# main.net
KiCad netlist of a schematic drawn in EAGLE
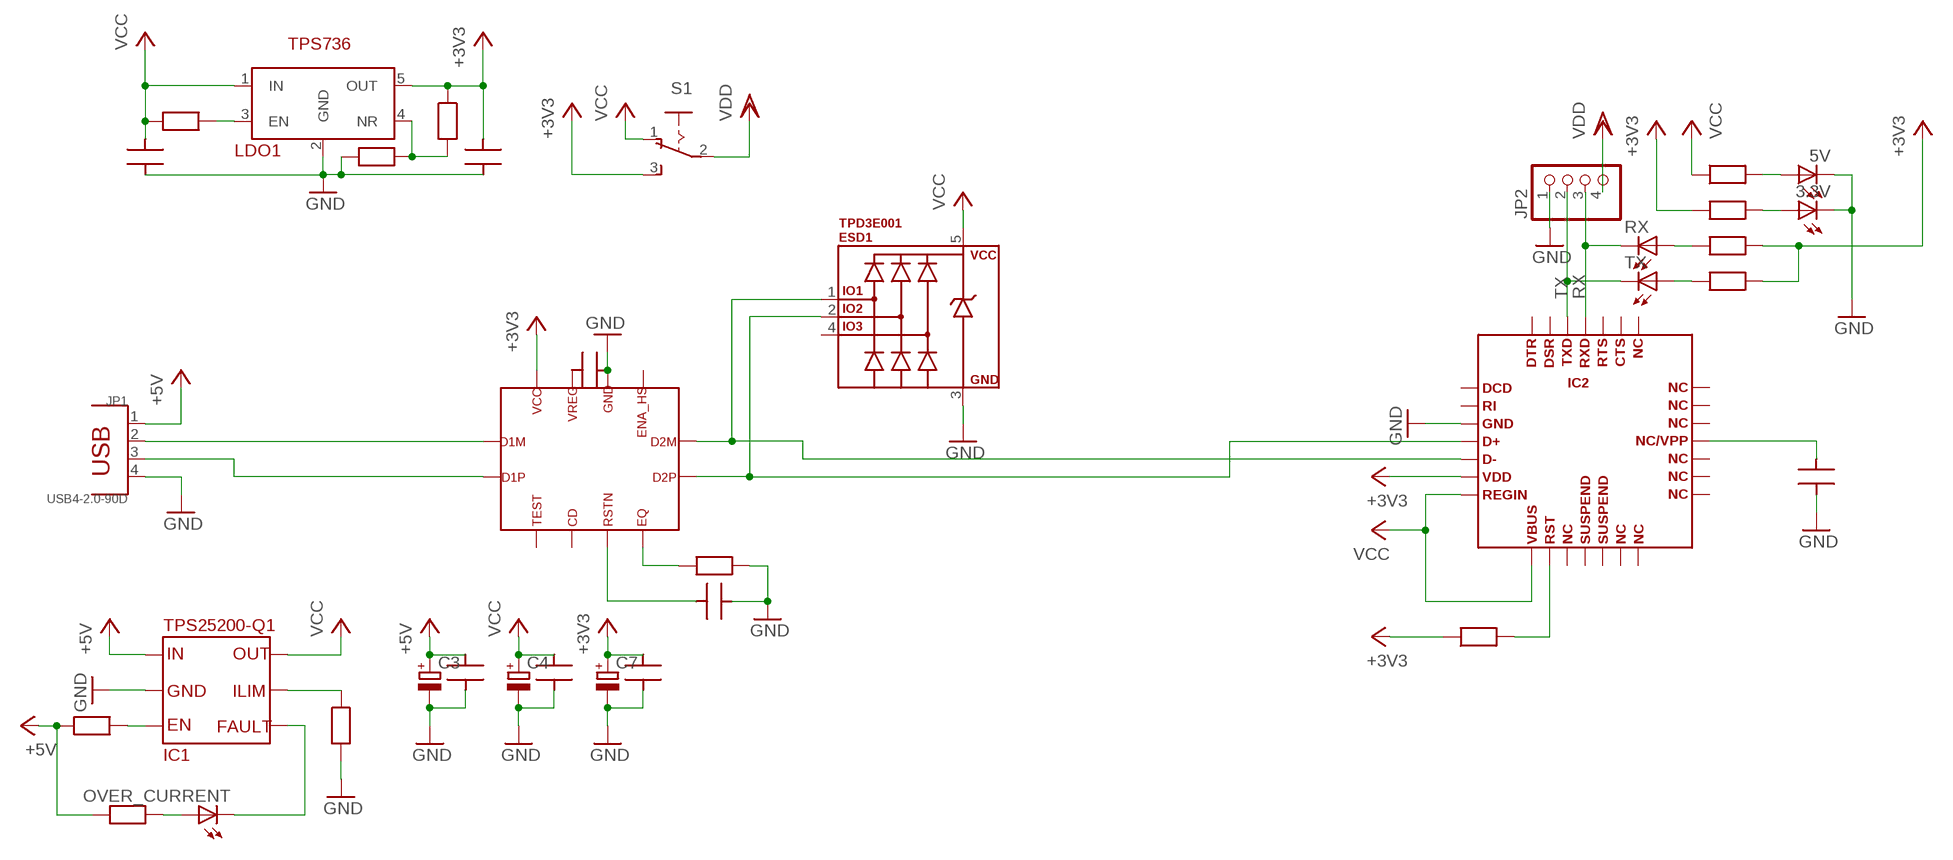
[diagram p0: schematic, sheet 1]

(export (version "E")
  (design (tool "Eeschema 10.0.6"))
  (components
    (comp (ref "3.3V")
      (value "LEDCHIP-LED0603")
      (footprint "eagle-import:CHIP-LED0603")
      (libsource (lib "eagle-import") (part "LEDCHIP-LED0603"))
    )
    (comp (ref "5V")
      (value "LEDCHIP-LED0603")
      (footprint "eagle-import:CHIP-LED0603")
      (libsource (lib "eagle-import") (part "LEDCHIP-LED0603"))
    )
    (comp (ref "C1")
      (value "CAP0603")
      (footprint "eagle-import:C0603")
      (libsource (lib "eagle-import") (part "CAP0603"))
    )
    (comp (ref "C2")
      (value "CAP0603")
      (footprint "eagle-import:C0603")
      (libsource (lib "eagle-import") (part "CAP0603"))
    )
    (comp (ref "C3")
      (value "CPOL-EUSMCA")
      (footprint "eagle-import:SMC_A")
      (libsource (lib "eagle-import") (part "CPOL-EUSMCA"))
    )
    (comp (ref "C4")
      (value "CPOL-EUSMCA")
      (footprint "eagle-import:SMC_A")
      (libsource (lib "eagle-import") (part "CPOL-EUSMCA"))
    )
    (comp (ref "C5")
      (value "CAP0603")
      (footprint "eagle-import:C0603")
      (libsource (lib "eagle-import") (part "CAP0603"))
    )
    (comp (ref "C6")
      (value "CAP0603")
      (footprint "eagle-import:C0603")
      (libsource (lib "eagle-import") (part "CAP0603"))
    )
    (comp (ref "C7")
      (value "CPOL-EUSMCA")
      (footprint "eagle-import:SMC_A")
      (libsource (lib "eagle-import") (part "CPOL-EUSMCA"))
    )
    (comp (ref "C8")
      (value "CAP0603")
      (footprint "eagle-import:C0603")
      (libsource (lib "eagle-import") (part "CAP0603"))
    )
    (comp (ref "C9")
      (value "CAP0603")
      (footprint "eagle-import:C0603")
      (libsource (lib "eagle-import") (part "CAP0603"))
    )
    (comp (ref "C10")
      (value "CAP0603")
      (footprint "eagle-import:C0603")
      (libsource (lib "eagle-import") (part "CAP0603"))
    )
    (comp (ref "C11")
      (value "CAP0603")
      (footprint "eagle-import:C0603")
      (libsource (lib "eagle-import") (part "CAP0603"))
    )
    (comp (ref "ESD1")
      (value "TPD3E001")
      (footprint "eagle-import:SOT23-5")
      (libsource (lib "eagle-import") (part "TPD3E001"))
    )
    (comp (ref "IC1")
      (value "TPS25200-Q1")
      (footprint "eagle-import:PWSON6")
      (libsource (lib "eagle-import") (part "TPS25200-Q1"))
    )
    (comp (ref "IC2")
      (value "CP2102/9")
      (footprint "eagle-import:QFN-28")
      (libsource (lib "eagle-import") (part "CP2102/9"))
    )
    (comp (ref "JP1")
      (value "USB4-2.0-90D")
      (footprint "eagle-import:USB4+2P-2.0-90D")
      (libsource (lib "eagle-import") (part "DIP-USB-A-TYPE-FMAL(4+2P-2.0-90D)"))
    )
    (comp (ref "JP2")
      (value "PINHD-1X4")
      (footprint "eagle-import:1X04")
      (libsource (lib "eagle-import") (part "PINHD-1X4"))
    )
    (comp (ref "LDO1")
      (value "TPS736")
      (footprint "eagle-import:SOT23-5")
      (libsource (lib "eagle-import") (part "TPS736"))
    )
    (comp (ref "OVER_CURRENT")
      (value "LEDCHIP-LED0603")
      (footprint "eagle-import:CHIP-LED0603")
      (libsource (lib "eagle-import") (part "LEDCHIP-LED0603"))
    )
    (comp (ref "R1")
      (value "RES0603")
      (footprint "eagle-import:R0603")
      (libsource (lib "eagle-import") (part "RES0603"))
    )
    (comp (ref "R2")
      (value "RES0603")
      (footprint "eagle-import:R0603")
      (libsource (lib "eagle-import") (part "RES0603"))
    )
    (comp (ref "R3")
      (value "RES0603")
      (footprint "eagle-import:R0603")
      (libsource (lib "eagle-import") (part "RES0603"))
    )
    (comp (ref "R4")
      (value "RES0603")
      (footprint "eagle-import:R0603")
      (libsource (lib "eagle-import") (part "RES0603"))
    )
    (comp (ref "R5")
      (value "RES0603")
      (footprint "eagle-import:R0603")
      (libsource (lib "eagle-import") (part "RES0603"))
    )
    (comp (ref "R6")
      (value "RES0603")
      (footprint "eagle-import:R0603")
      (libsource (lib "eagle-import") (part "RES0603"))
    )
    (comp (ref "R7")
      (value "RES0603")
      (footprint "eagle-import:R0603")
      (libsource (lib "eagle-import") (part "RES0603"))
    )
    (comp (ref "R8")
      (value "RES0603")
      (footprint "eagle-import:R0603")
      (libsource (lib "eagle-import") (part "RES0603"))
    )
    (comp (ref "R9")
      (value "RES0603")
      (footprint "eagle-import:R0603")
      (libsource (lib "eagle-import") (part "RES0603"))
    )
    (comp (ref "R10")
      (value "RES0603")
      (footprint "eagle-import:R0603")
      (libsource (lib "eagle-import") (part "RES0603"))
    )
    (comp (ref "R11")
      (value "RES0603")
      (footprint "eagle-import:R0603")
      (libsource (lib "eagle-import") (part "RES0603"))
    )
    (comp (ref "R12")
      (value "RES0603")
      (footprint "eagle-import:R0603")
      (libsource (lib "eagle-import") (part "RES0603"))
    )
    (comp (ref "RX")
      (value "LEDCHIP-LED0603")
      (footprint "eagle-import:CHIP-LED0603")
      (libsource (lib "eagle-import") (part "LEDCHIP-LED0603"))
    )
    (comp (ref "S1")
      (value "255SB")
      (footprint "eagle-import:255SB")
      (libsource (lib "eagle-import") (part "255SB"))
    )
    (comp (ref "TX")
      (value "LEDCHIP-LED0603")
      (footprint "eagle-import:CHIP-LED0603")
      (libsource (lib "eagle-import") (part "LEDCHIP-LED0603"))
    )
    (comp (ref "USB1")
      (value "TUSB211QRWBRQ1")
      (footprint "eagle-import:X2QFN")
      (libsource (lib "eagle-import") (part "TUSB211QRWBRQ1"))
    )
  )
  (nets
    (net (code "1") (name "+3V3") (class "Default")
      (node (ref "C2") (pin "2") (pinfunction "P$2_2") (pintype "bidirectional"))
      (node (ref "C7") (pin "+") (pinfunction "+_+") (pintype "passive"))
      (node (ref "C8") (pin "2") (pinfunction "P$2_2") (pintype "bidirectional"))
      (node (ref "IC2") (pin "6") (pinfunction "P$6_6") (pintype "bidirectional"))
      (node (ref "LDO1") (pin "5") (pinfunction "OUT_5") (pintype "bidirectional"))
      (node (ref "R10") (pin "1") (pinfunction "P$1_1") (pintype "bidirectional"))
      (node (ref "R2") (pin "1") (pinfunction "P$1_1") (pintype "bidirectional"))
      (node (ref "R7") (pin "1") (pinfunction "P$1_1") (pintype "bidirectional"))
      (node (ref "R8") (pin "2") (pinfunction "P$2_2") (pintype "bidirectional"))
      (node (ref "R9") (pin "2") (pinfunction "P$2_2") (pintype "bidirectional"))
      (node (ref "S1") (pin "3") (pinfunction "S_3") (pintype "passive"))
      (node (ref "USB1") (pin "12") (pinfunction "P$12_12") (pintype "bidirectional"))
    )
    (net (code "2") (name "+5V") (class "Default")
      (node (ref "C3") (pin "+") (pinfunction "+_+") (pintype "passive"))
      (node (ref "C5") (pin "2") (pinfunction "P$2_2") (pintype "bidirectional"))
      (node (ref "IC1") (pin "P$1") (pinfunction "P$1_P$1") (pintype "bidirectional"))
      (node (ref "JP1") (pin "1") (pinfunction "1_1") (pintype "bidirectional"))
      (node (ref "R12") (pin "1") (pinfunction "P$1_1") (pintype "bidirectional"))
      (node (ref "R4") (pin "2") (pinfunction "P$2_2") (pintype "bidirectional"))
    )
    (net (code "3") (name "/RX") (class "Default")
      (node (ref "IC2") (pin "25") (pinfunction "P$25_25") (pintype "bidirectional"))
      (node (ref "JP2") (pin "3") (pinfunction "3_3") (pintype "passive"))
      (node (ref "RX") (pin "C") (pinfunction "C_C") (pintype "passive"))
    )
    (net (code "4") (name "/TX") (class "Default")
      (node (ref "IC2") (pin "26") (pinfunction "P$26_26") (pintype "bidirectional"))
      (node (ref "JP2") (pin "2") (pinfunction "2_2") (pintype "passive"))
      (node (ref "TX") (pin "C") (pinfunction "C_C") (pintype "passive"))
    )
    (net (code "5") (name "GND") (class "Default")
      (node (ref "3.3V") (pin "C") (pinfunction "C_C") (pintype "passive"))
      (node (ref "5V") (pin "C") (pinfunction "C_C") (pintype "passive"))
      (node (ref "C1") (pin "1") (pinfunction "P$1_1") (pintype "bidirectional"))
      (node (ref "C10") (pin "1") (pinfunction "P$1_1") (pintype "bidirectional"))
      (node (ref "C11") (pin "2") (pinfunction "P$2_2") (pintype "bidirectional"))
      (node (ref "C2") (pin "1") (pinfunction "P$1_1") (pintype "bidirectional"))
      (node (ref "C3") (pin "-") (pinfunction "-_-") (pintype "passive"))
      (node (ref "C4") (pin "-") (pinfunction "-_-") (pintype "passive"))
      (node (ref "C5") (pin "1") (pinfunction "P$1_1") (pintype "bidirectional"))
      (node (ref "C6") (pin "1") (pinfunction "P$1_1") (pintype "bidirectional"))
      (node (ref "C7") (pin "-") (pinfunction "-_-") (pintype "passive"))
      (node (ref "C8") (pin "1") (pinfunction "P$1_1") (pintype "bidirectional"))
      (node (ref "C9") (pin "1") (pinfunction "P$1_1") (pintype "bidirectional"))
      (node (ref "ESD1") (pin "3") (pinfunction "3_3") (pintype "bidirectional"))
      (node (ref "IC1") (pin "EPAD") (pinfunction "P$2_EPAD") (pintype "bidirectional"))
      (node (ref "IC1") (pin "P$2") (pinfunction "P$2_P$2") (pintype "bidirectional"))
      (node (ref "IC2") (pin "3") (pinfunction "P$3_3") (pintype "bidirectional"))
      (node (ref "IC2") (pin "EPAD_B") (pinfunction "P$3_EPAD_B") (pintype "bidirectional"))
      (node (ref "IC2") (pin "EPAD_T") (pinfunction "P$3_EPAD_T") (pintype "bidirectional"))
      (node (ref "IC2") (pin "EPAD_VIA1") (pinfunction "P$3_EPAD_VIA1") (pintype "bidirectional"))
      (node (ref "IC2") (pin "EPAD_VIA2") (pinfunction "P$3_EPAD_VIA2") (pintype "bidirectional"))
      (node (ref "IC2") (pin "EPAD_VIA3") (pinfunction "P$3_EPAD_VIA3") (pintype "bidirectional"))
      (node (ref "IC2") (pin "EPAD_VIA4") (pinfunction "P$3_EPAD_VIA4") (pintype "bidirectional"))
      (node (ref "IC2") (pin "EPAD_VIA5") (pinfunction "P$3_EPAD_VIA5") (pintype "bidirectional"))
      (node (ref "IC2") (pin "EPAD_VIA6") (pinfunction "P$3_EPAD_VIA6") (pintype "bidirectional"))
      (node (ref "IC2") (pin "EPAD_VIA7") (pinfunction "P$3_EPAD_VIA7") (pintype "bidirectional"))
      (node (ref "IC2") (pin "EPAD_VIA8") (pinfunction "P$3_EPAD_VIA8") (pintype "bidirectional"))
      (node (ref "IC2") (pin "EPAD_VIA9") (pinfunction "P$3_EPAD_VIA9") (pintype "bidirectional"))
      (node (ref "JP1") (pin "4") (pinfunction "4_4") (pintype "bidirectional"))
      (node (ref "JP2") (pin "1") (pinfunction "1_1") (pintype "passive"))
      (node (ref "LDO1") (pin "2") (pinfunction "GND_2") (pintype "bidirectional"))
      (node (ref "R3") (pin "1") (pinfunction "P$1_1") (pintype "bidirectional"))
      (node (ref "R5") (pin "2") (pinfunction "P$2_2") (pintype "bidirectional"))
      (node (ref "R6") (pin "2") (pinfunction "P$2_2") (pintype "bidirectional"))
      (node (ref "USB1") (pin "10") (pinfunction "P$10_10") (pintype "bidirectional"))
    )
    (net (code "6") (name "Net-(C9-P$2)") (class "Default")
      (node (ref "C9") (pin "2") (pinfunction "P$2_2") (pintype "bidirectional"))
      (node (ref "USB1") (pin "11") (pinfunction "P$11_11") (pintype "bidirectional"))
    )
    (net (code "7") (name "Net-(C10-P$2)") (class "Default")
      (node (ref "C10") (pin "2") (pinfunction "P$2_2") (pintype "bidirectional"))
      (node (ref "USB1") (pin "5") (pinfunction "P$5_5") (pintype "bidirectional"))
    )
    (net (code "8") (name "Net-(C11-P$1)") (class "Default")
      (node (ref "C11") (pin "1") (pinfunction "P$1_1") (pintype "bidirectional"))
      (node (ref "IC2") (pin "18") (pinfunction "P$18_18") (pintype "bidirectional"))
    )
    (net (code "9") (name "Net-(IC1-PadP$4)") (class "Default")
      (node (ref "IC1") (pin "P$4") (pinfunction "P$4_P$4") (pintype "bidirectional"))
      (node (ref "OVER_CURRENT") (pin "C") (pinfunction "C_C") (pintype "passive"))
    )
    (net (code "10") (name "Net-(IC2-P$4)") (class "Default")
      (node (ref "ESD1") (pin "2") (pinfunction "2_2") (pintype "bidirectional"))
      (node (ref "IC2") (pin "4") (pinfunction "P$4_4") (pintype "bidirectional"))
      (node (ref "USB1") (pin "7") (pinfunction "P$7_7") (pintype "bidirectional"))
    )
    (net (code "11") (name "Net-(IC2-P$5)") (class "Default")
      (node (ref "ESD1") (pin "1") (pinfunction "1_1") (pintype "bidirectional"))
      (node (ref "IC2") (pin "5") (pinfunction "P$5_5") (pintype "bidirectional"))
      (node (ref "USB1") (pin "8") (pinfunction "P$8_8") (pintype "bidirectional"))
    )
    (net (code "12") (name "Net-(IC2-P$9)") (class "Default")
      (node (ref "IC2") (pin "9") (pinfunction "P$9_9") (pintype "bidirectional"))
      (node (ref "R7") (pin "2") (pinfunction "P$2_2") (pintype "bidirectional"))
    )
    (net (code "13") (name "Net-(LDO1-EN)") (class "Default")
      (node (ref "LDO1") (pin "3") (pinfunction "EN_3") (pintype "bidirectional"))
      (node (ref "R1") (pin "1") (pinfunction "P$1_1") (pintype "bidirectional"))
    )
    (net (code "14") (name "Net-(LDO1-NR)") (class "Default")
      (node (ref "LDO1") (pin "4") (pinfunction "NR_4") (pintype "bidirectional"))
      (node (ref "R2") (pin "2") (pinfunction "P$2_2") (pintype "bidirectional"))
      (node (ref "R3") (pin "2") (pinfunction "P$2_2") (pintype "bidirectional"))
    )
    (net (code "15") (name "Net-(R4-P$1)") (class "Default")
      (node (ref "IC1") (pin "P$3") (pinfunction "P$3_P$3") (pintype "bidirectional"))
      (node (ref "R4") (pin "1") (pinfunction "P$1_1") (pintype "bidirectional"))
    )
    (net (code "16") (name "Net-(R5-P$1)") (class "Default")
      (node (ref "IC1") (pin "P$5") (pinfunction "P$5_P$5") (pintype "bidirectional"))
      (node (ref "R5") (pin "1") (pinfunction "P$1_1") (pintype "bidirectional"))
    )
    (net (code "17") (name "Net-(R6-P$1)") (class "Default")
      (node (ref "R6") (pin "1") (pinfunction "P$1_1") (pintype "bidirectional"))
      (node (ref "USB1") (pin "6") (pinfunction "P$6_6") (pintype "bidirectional"))
    )
    (net (code "18") (name "Net-(R8-P$1)") (class "Default")
      (node (ref "R8") (pin "1") (pinfunction "P$1_1") (pintype "bidirectional"))
      (node (ref "RX") (pin "A") (pinfunction "A_A") (pintype "passive"))
    )
    (net (code "19") (name "Net-(R9-P$1)") (class "Default")
      (node (ref "R9") (pin "1") (pinfunction "P$1_1") (pintype "bidirectional"))
      (node (ref "TX") (pin "A") (pinfunction "A_A") (pintype "passive"))
    )
    (net (code "20") (name "Net-(R10-P$2)") (class "Default")
      (node (ref "3.3V") (pin "A") (pinfunction "A_A") (pintype "passive"))
      (node (ref "R10") (pin "2") (pinfunction "P$2_2") (pintype "bidirectional"))
    )
    (net (code "21") (name "Net-(R11-P$2)") (class "Default")
      (node (ref "5V") (pin "A") (pinfunction "A_A") (pintype "passive"))
      (node (ref "R11") (pin "2") (pinfunction "P$2_2") (pintype "bidirectional"))
    )
    (net (code "22") (name "Net-(R12-P$2)") (class "Default")
      (node (ref "OVER_CURRENT") (pin "A") (pinfunction "A_A") (pintype "passive"))
      (node (ref "R12") (pin "2") (pinfunction "P$2_2") (pintype "bidirectional"))
    )
    (net (code "23") (name "Net-(USB1-P$1)") (class "Default")
      (node (ref "JP1") (pin "2") (pinfunction "2_2") (pintype "bidirectional"))
      (node (ref "USB1") (pin "1") (pinfunction "P$1_1") (pintype "bidirectional"))
    )
    (net (code "24") (name "Net-(USB1-P$2)") (class "Default")
      (node (ref "JP1") (pin "3") (pinfunction "3_3") (pintype "bidirectional"))
      (node (ref "USB1") (pin "2") (pinfunction "P$2_2") (pintype "bidirectional"))
    )
    (net (code "25") (name "VCC") (class "Default")
      (node (ref "C1") (pin "2") (pinfunction "P$2_2") (pintype "bidirectional"))
      (node (ref "C4") (pin "+") (pinfunction "+_+") (pintype "passive"))
      (node (ref "C6") (pin "2") (pinfunction "P$2_2") (pintype "bidirectional"))
      (node (ref "ESD1") (pin "5") (pinfunction "5_5") (pintype "bidirectional"))
      (node (ref "IC1") (pin "P$6") (pinfunction "P$6_P$6") (pintype "bidirectional"))
      (node (ref "IC2") (pin "7") (pinfunction "P$7_7") (pintype "bidirectional"))
      (node (ref "IC2") (pin "8") (pinfunction "P$8_8") (pintype "bidirectional"))
      (node (ref "LDO1") (pin "1") (pinfunction "IN_1") (pintype "bidirectional"))
      (node (ref "R1") (pin "2") (pinfunction "P$2_2") (pintype "bidirectional"))
      (node (ref "R11") (pin "1") (pinfunction "P$1_1") (pintype "bidirectional"))
      (node (ref "S1") (pin "1") (pinfunction "O_1") (pintype "passive"))
    )
    (net (code "26") (name "VDD") (class "Default")
      (node (ref "JP2") (pin "4") (pinfunction "4_4") (pintype "passive"))
      (node (ref "S1") (pin "2") (pinfunction "P_2") (pintype "passive"))
    )
    (net (code "27") (name "unconnected-(ESD1-Pad4)") (class "Default")
      (node (ref "ESD1") (pin "4") (pinfunction "4_4") (pintype "bidirectional"))
    )
    (net (code "28") (name "unconnected-(IC2-P$1-Pad1)") (class "Default")
      (node (ref "IC2") (pin "1") (pinfunction "P$1_1") (pintype "bidirectional"))
    )
    (net (code "29") (name "unconnected-(IC2-P$2-Pad2)") (class "Default")
      (node (ref "IC2") (pin "2") (pinfunction "P$2_2") (pintype "bidirectional"))
    )
    (net (code "30") (name "unconnected-(IC2-P$10-Pad10)") (class "Default")
      (node (ref "IC2") (pin "10") (pinfunction "P$10_10") (pintype "bidirectional"))
    )
    (net (code "31") (name "unconnected-(IC2-P$11-Pad11)") (class "Default")
      (node (ref "IC2") (pin "11") (pinfunction "P$11_11") (pintype "bidirectional"))
    )
    (net (code "32") (name "unconnected-(IC2-P$12-Pad12)") (class "Default")
      (node (ref "IC2") (pin "12") (pinfunction "P$12_12") (pintype "bidirectional"))
    )
    (net (code "33") (name "unconnected-(IC2-P$13-Pad13)") (class "Default")
      (node (ref "IC2") (pin "13") (pinfunction "P$13_13") (pintype "bidirectional"))
    )
    (net (code "34") (name "unconnected-(IC2-P$14-Pad14)") (class "Default")
      (node (ref "IC2") (pin "14") (pinfunction "P$14_14") (pintype "bidirectional"))
    )
    (net (code "35") (name "unconnected-(IC2-P$15-Pad15)") (class "Default")
      (node (ref "IC2") (pin "15") (pinfunction "P$15_15") (pintype "bidirectional"))
    )
    (net (code "36") (name "unconnected-(IC2-P$16-Pad16)") (class "Default")
      (node (ref "IC2") (pin "16") (pinfunction "P$16_16") (pintype "bidirectional"))
    )
    (net (code "37") (name "unconnected-(IC2-P$17-Pad17)") (class "Default")
      (node (ref "IC2") (pin "17") (pinfunction "P$17_17") (pintype "bidirectional"))
    )
    (net (code "38") (name "unconnected-(IC2-P$19-Pad19)") (class "Default")
      (node (ref "IC2") (pin "19") (pinfunction "P$19_19") (pintype "bidirectional"))
    )
    (net (code "39") (name "unconnected-(IC2-P$20-Pad20)") (class "Default")
      (node (ref "IC2") (pin "20") (pinfunction "P$20_20") (pintype "bidirectional"))
    )
    (net (code "40") (name "unconnected-(IC2-P$21-Pad21)") (class "Default")
      (node (ref "IC2") (pin "21") (pinfunction "P$21_21") (pintype "bidirectional"))
    )
    (net (code "41") (name "unconnected-(IC2-P$22-Pad22)") (class "Default")
      (node (ref "IC2") (pin "22") (pinfunction "P$22_22") (pintype "bidirectional"))
    )
    (net (code "42") (name "unconnected-(IC2-P$23-Pad23)") (class "Default")
      (node (ref "IC2") (pin "23") (pinfunction "P$23_23") (pintype "bidirectional"))
    )
    (net (code "43") (name "unconnected-(IC2-P$24-Pad24)") (class "Default")
      (node (ref "IC2") (pin "24") (pinfunction "P$24_24") (pintype "bidirectional"))
    )
    (net (code "44") (name "unconnected-(IC2-P$27-Pad27)") (class "Default")
      (node (ref "IC2") (pin "27") (pinfunction "P$27_27") (pintype "bidirectional"))
    )
    (net (code "45") (name "unconnected-(IC2-P$28-Pad28)") (class "Default")
      (node (ref "IC2") (pin "28") (pinfunction "P$28_28") (pintype "bidirectional"))
    )
    (net (code "46") (name "unconnected-(USB1-P$3-Pad3)") (class "Default")
      (node (ref "USB1") (pin "3") (pinfunction "P$3_3") (pintype "bidirectional"))
    )
    (net (code "47") (name "unconnected-(USB1-P$4-Pad4)") (class "Default")
      (node (ref "USB1") (pin "4") (pinfunction "P$4_4") (pintype "bidirectional"))
    )
    (net (code "48") (name "unconnected-(USB1-P$9-Pad9)") (class "Default")
      (node (ref "USB1") (pin "9") (pinfunction "P$9_9") (pintype "bidirectional"))
    )
  )
)
